# uproszczony_odbiornik.net
KiCad netlist of a schematic drawn in EAGLE
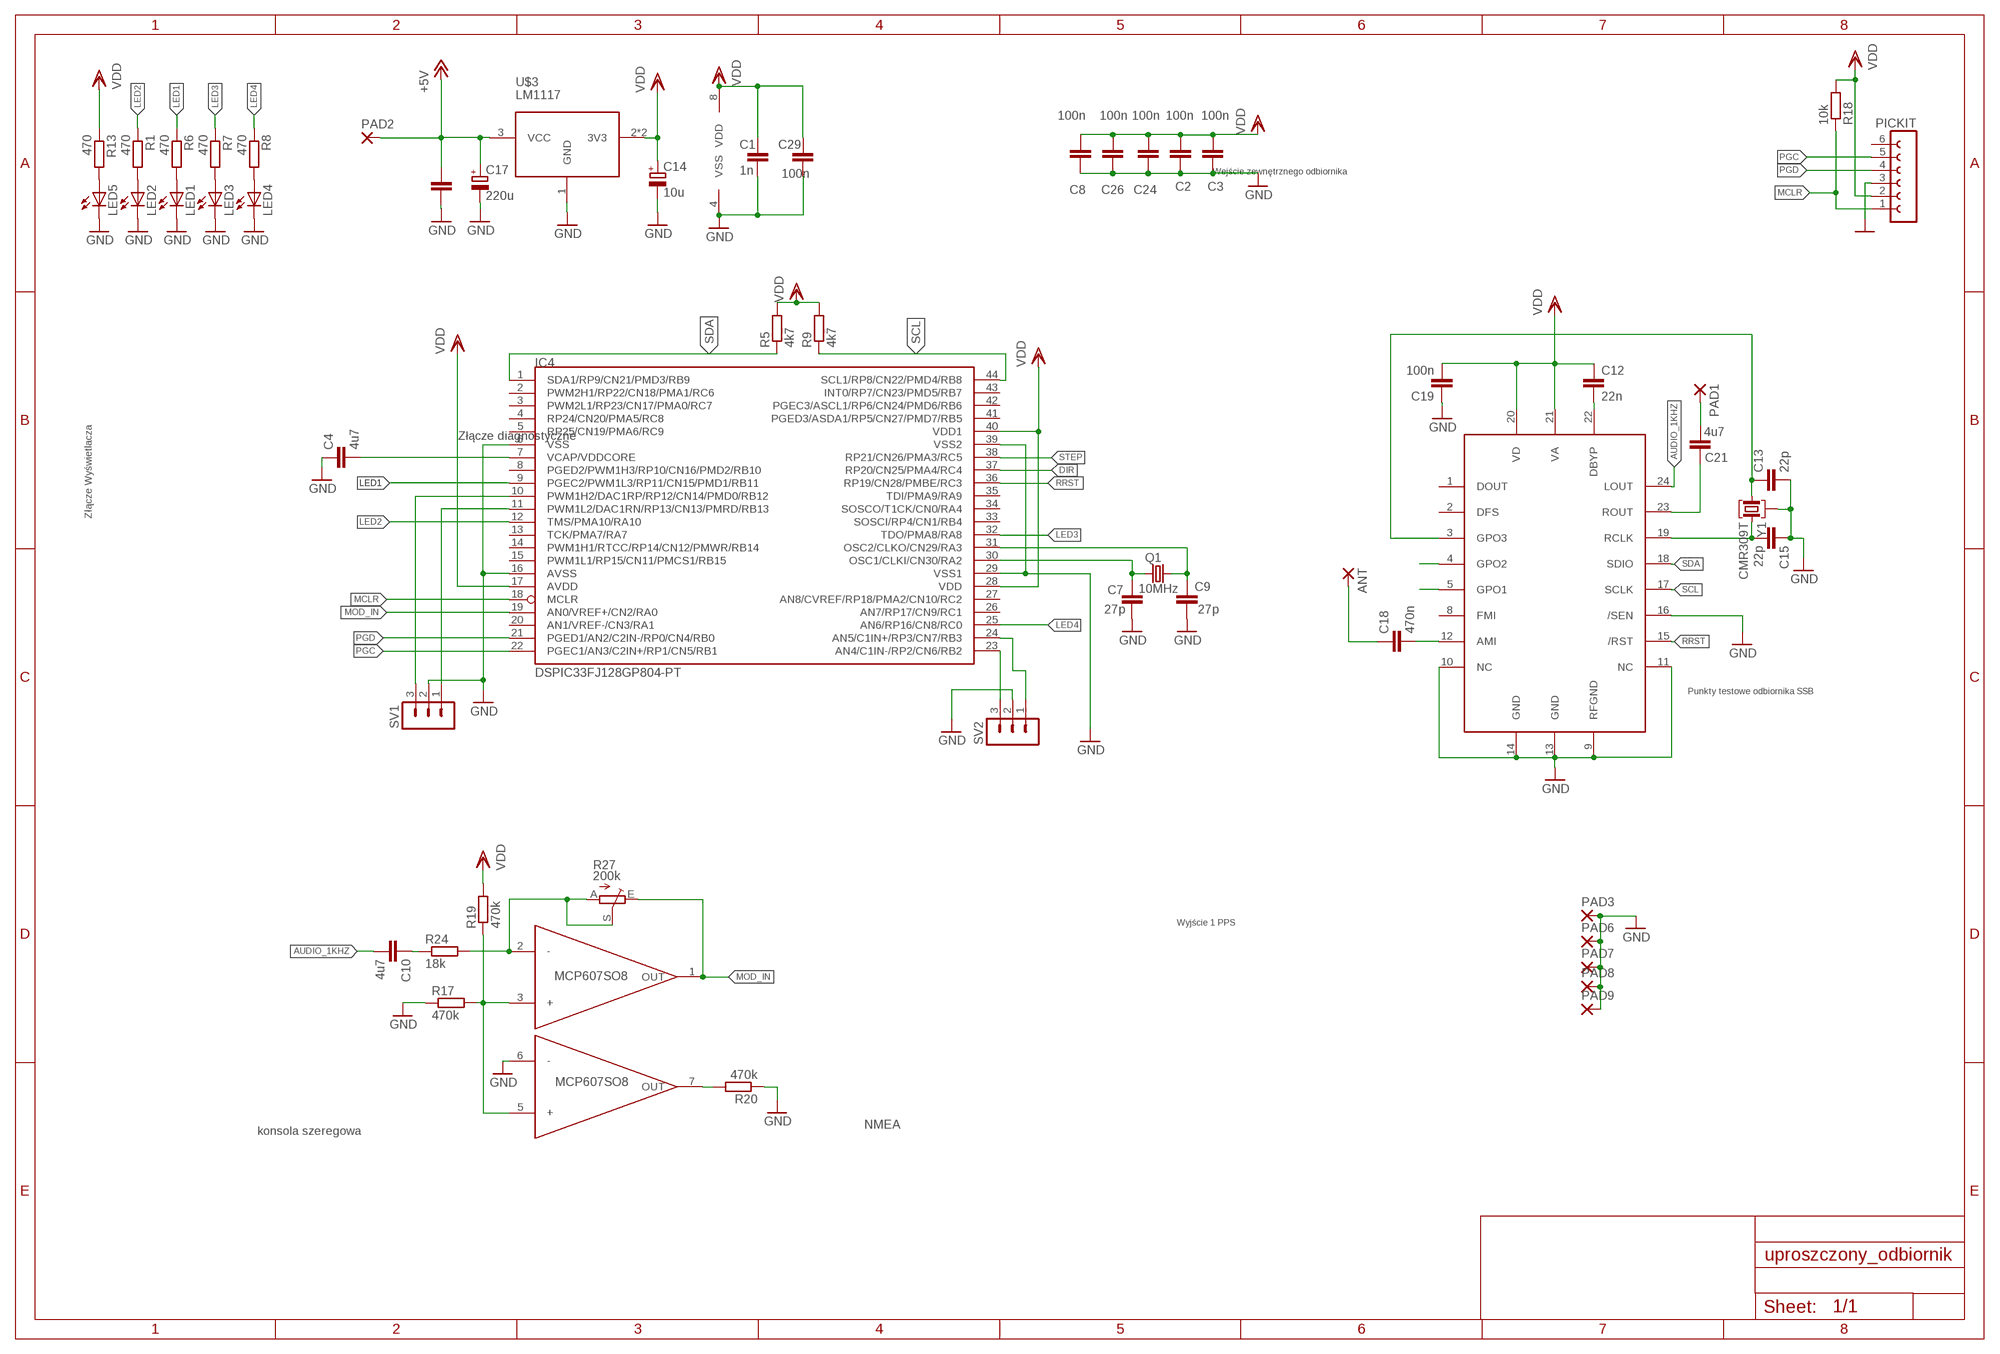
[diagram p0: schematic, sheet 1]

(export (version "E")
  (design (tool "Eeschema 10.0.6"))
  (components
    (comp (ref "ANT")
      (value "1,6/0,9")
      (footprint "eagle-import:1,6_0,9")
      (libsource (lib "eagle-import") (part "1,6/0,9"))
    )
    (comp (ref "C1")
      (value "1n")
      (footprint "eagle-import:C0805K")
      (libsource (lib "eagle-import") (part "C-EUC0805K"))
    )
    (comp (ref "C2")
      (value "100n")
      (footprint "eagle-import:C0805K")
      (libsource (lib "eagle-import") (part "C-EUC0805K"))
    )
    (comp (ref "C3")
      (value "100n")
      (footprint "eagle-import:C0805K")
      (libsource (lib "eagle-import") (part "C-EUC0805K"))
    )
    (comp (ref "C4")
      (value "4u7")
      (footprint "eagle-import:C0805K")
      (libsource (lib "eagle-import") (part "C-EUC0805K"))
    )
    (comp (ref "C5")
      (value "100n")
      (footprint "eagle-import:C0805K")
      (libsource (lib "eagle-import") (part "C-EUC0805K"))
    )
    (comp (ref "C7")
      (value "27p")
      (footprint "eagle-import:C0805K")
      (libsource (lib "eagle-import") (part "C-EUC0805K"))
    )
    (comp (ref "C8")
      (value "100n")
      (footprint "eagle-import:C0805K")
      (libsource (lib "eagle-import") (part "C-EUC0805K"))
    )
    (comp (ref "C9")
      (value "27p")
      (footprint "eagle-import:C0805K")
      (libsource (lib "eagle-import") (part "C-EUC0805K"))
    )
    (comp (ref "C10")
      (value "4u7")
      (footprint "eagle-import:C0603K")
      (libsource (lib "eagle-import") (part "C-EUC0603K"))
    )
    (comp (ref "C12")
      (value "22n")
      (footprint "eagle-import:C0603K")
      (libsource (lib "eagle-import") (part "C-EUC0603K"))
    )
    (comp (ref "C13")
      (value "22p")
      (footprint "eagle-import:C0603K")
      (libsource (lib "eagle-import") (part "C-EUC0603K"))
    )
    (comp (ref "C14")
      (value "10u")
      (footprint "eagle-import:SMC_B")
      (libsource (lib "eagle-import") (part "CPOL-EUSMCB"))
    )
    (comp (ref "C15")
      (value "22p")
      (footprint "eagle-import:C0603K")
      (libsource (lib "eagle-import") (part "C-EUC0603K"))
    )
    (comp (ref "C17")
      (value "220u")
      (footprint "eagle-import:SMC_B")
      (libsource (lib "eagle-import") (part "CPOL-EUSMCB"))
    )
    (comp (ref "C18")
      (value "470n")
      (footprint "eagle-import:C0603K")
      (libsource (lib "eagle-import") (part "C-EUC0603K"))
    )
    (comp (ref "C19")
      (value "100n")
      (footprint "eagle-import:C0603K")
      (libsource (lib "eagle-import") (part "C-EUC0603K"))
    )
    (comp (ref "C21")
      (value "4u7")
      (footprint "eagle-import:C0603K")
      (libsource (lib "eagle-import") (part "C-EUC0603K"))
    )
    (comp (ref "C24")
      (value "100n")
      (footprint "eagle-import:C0805K")
      (libsource (lib "eagle-import") (part "C-EUC0805K"))
    )
    (comp (ref "C26")
      (value "100n")
      (footprint "eagle-import:C0805K")
      (libsource (lib "eagle-import") (part "C-EUC0805K"))
    )
    (comp (ref "C29")
      (value "100n")
      (footprint "eagle-import:C0805K")
      (libsource (lib "eagle-import") (part "C-EUC0805K"))
    )
    (comp (ref "IC4")
      (value "DSPIC33FJ128GP804-PT")
      (footprint "eagle-import:TQFP44")
      (libsource (lib "eagle-import") (part "DSPIC33FJ64MC804-PT"))
    )
    (comp (ref "LED1")
      (value "LEDCHIP-LED0805")
      (footprint "eagle-import:CHIP-LED0805")
      (libsource (lib "eagle-import") (part "LEDCHIP-LED0805"))
    )
    (comp (ref "LED2")
      (value "LEDCHIP-LED0805")
      (footprint "eagle-import:CHIP-LED0805")
      (libsource (lib "eagle-import") (part "LEDCHIP-LED0805"))
    )
    (comp (ref "LED3")
      (value "LEDCHIP-LED0805")
      (footprint "eagle-import:CHIP-LED0805")
      (libsource (lib "eagle-import") (part "LEDCHIP-LED0805"))
    )
    (comp (ref "LED4")
      (value "LEDCHIP-LED0805")
      (footprint "eagle-import:CHIP-LED0805")
      (libsource (lib "eagle-import") (part "LEDCHIP-LED0805"))
    )
    (comp (ref "LED5")
      (value "LEDCHIP-LED0805")
      (footprint "eagle-import:CHIP-LED0805")
      (libsource (lib "eagle-import") (part "LEDCHIP-LED0805"))
    )
    (comp (ref "PAD1")
      (value "1,6/0,9")
      (footprint "eagle-import:1,6_0,9")
      (libsource (lib "eagle-import") (part "1,6/0,9"))
    )
    (comp (ref "PAD2")
      (value "1,6/0,9")
      (footprint "eagle-import:1,6_0,9")
      (libsource (lib "eagle-import") (part "1,6/0,9"))
    )
    (comp (ref "PAD3")
      (value "1,6/0,9")
      (footprint "eagle-import:1,6_0,9")
      (libsource (lib "eagle-import") (part "1,6/0,9"))
    )
    (comp (ref "PAD6")
      (value "1,6/0,9")
      (footprint "eagle-import:1,6_0,9")
      (libsource (lib "eagle-import") (part "1,6/0,9"))
    )
    (comp (ref "PAD7")
      (value "1,6/0,9")
      (footprint "eagle-import:1,6_0,9")
      (libsource (lib "eagle-import") (part "1,6/0,9"))
    )
    (comp (ref "PAD8")
      (value "1,6/0,9")
      (footprint "eagle-import:1,6_0,9")
      (libsource (lib "eagle-import") (part "1,6/0,9"))
    )
    (comp (ref "PAD9")
      (value "1,6/0,9")
      (footprint "eagle-import:1,6_0,9")
      (libsource (lib "eagle-import") (part "1,6/0,9"))
    )
    (comp (ref "PICKIT")
      (value "FE06-1")
      (footprint "eagle-import:FE06")
      (libsource (lib "eagle-import") (part "FE06-1"))
    )
    (comp (ref "Q1")
      (value "10MHz")
      (footprint "eagle-import:HC49U-V")
      (libsource (lib "eagle-import") (part "CRYSTALHC49U-V"))
    )
    (comp (ref "R1")
      (value "470")
      (footprint "eagle-import:R0805")
      (libsource (lib "eagle-import") (part "R-EU_R0805"))
    )
    (comp (ref "R5")
      (value "4k7")
      (footprint "eagle-import:R0805")
      (libsource (lib "eagle-import") (part "R-EU_R0805"))
    )
    (comp (ref "R6")
      (value "470")
      (footprint "eagle-import:R0805")
      (libsource (lib "eagle-import") (part "R-EU_R0805"))
    )
    (comp (ref "R7")
      (value "470")
      (footprint "eagle-import:R0805")
      (libsource (lib "eagle-import") (part "R-EU_R0805"))
    )
    (comp (ref "R8")
      (value "470")
      (footprint "eagle-import:R0805")
      (libsource (lib "eagle-import") (part "R-EU_R0805"))
    )
    (comp (ref "R9")
      (value "4k7")
      (footprint "eagle-import:R0805")
      (libsource (lib "eagle-import") (part "R-EU_R0805"))
    )
    (comp (ref "R13")
      (value "470")
      (footprint "eagle-import:R0805")
      (libsource (lib "eagle-import") (part "R-EU_R0805"))
    )
    (comp (ref "R17")
      (value "470k")
      (footprint "eagle-import:M0805")
      (libsource (lib "eagle-import") (part "R-EU_M0805"))
    )
    (comp (ref "R18")
      (value "10k")
      (footprint "eagle-import:R0805")
      (libsource (lib "eagle-import") (part "R-EU_R0805"))
    )
    (comp (ref "R19")
      (value "470k")
      (footprint "eagle-import:M0805")
      (libsource (lib "eagle-import") (part "R-EU_M0805"))
    )
    (comp (ref "R20")
      (value "470k")
      (footprint "eagle-import:M0805")
      (libsource (lib "eagle-import") (part "R-EU_M0805"))
    )
    (comp (ref "R24")
      (value "18k")
      (footprint "eagle-import:M0805")
      (libsource (lib "eagle-import") (part "R-EU_M0805"))
    )
    (comp (ref "R27")
      (value "200k")
      (footprint "eagle-import:RJ9W")
      (libsource (lib "eagle-import") (part "TRIM_EU-RJ9W"))
    )
    (comp (ref "SV1")
      (value "MA03-1")
      (footprint "eagle-import:MA03-1")
      (libsource (lib "eagle-import") (part "MA03-1"))
    )
    (comp (ref "SV2")
      (value "MA03-1")
      (footprint "eagle-import:MA03-1")
      (libsource (lib "eagle-import") (part "MA03-1"))
    )
    (comp (ref "U$1")
      (value "MCP607SO8")
      (footprint "eagle-import:SOIC8")
      (libsource (lib "eagle-import") (part "MCP607SO8"))
    )
    (comp (ref "U$3")
      (value "LM1117")
      (footprint "eagle-import:SOT223-3")
      (libsource (lib "eagle-import") (part "LM1117"))
    )
    (comp (ref "U$5")
      (value "SI4735-D60")
      (footprint "eagle-import:SSOP24")
      (libsource (lib "eagle-import") (part "SI4735-D60"))
    )
    (comp (ref "Y1")
      (value "CMR309T")
      (footprint "eagle-import:CMR309T")
      (libsource (lib "eagle-import") (part "CMR309T"))
    )
  )
  (nets
    (net (code "1") (name "+5V") (class "Default")
      (node (ref "C17") (pin "+") (pinfunction "+_+") (pintype "passive"))
      (node (ref "C5") (pin "1") (pinfunction "1_1") (pintype "passive"))
      (node (ref "PAD2") (pin "1") (pinfunction "P_1") (pintype "passive"))
      (node (ref "U$3") (pin "3") (pinfunction "VCC_3") (pintype "power_in"))
    )
    (net (code "2") (name "AUDIO_1KHZ") (class "Default")
      (node (ref "C10") (pin "2") (pinfunction "2_2") (pintype "passive"))
      (node (ref "U$5") (pin "24") (pinfunction "LOUT_24") (pintype "power_in"))
    )
    (net (code "3") (name "DIR") (class "Default")
      (node (ref "IC4") (pin "37") (pinfunction "RP20/CN25/PMA4/RC4_37") (pintype "bidirectional"))
    )
    (net (code "4") (name "GND") (class "Default")
      (node (ref "C1") (pin "2") (pinfunction "2_2") (pintype "passive"))
      (node (ref "C13") (pin "2") (pinfunction "2_2") (pintype "passive"))
      (node (ref "C14") (pin "-") (pinfunction "-_-") (pintype "passive"))
      (node (ref "C15") (pin "1") (pinfunction "1_1") (pintype "passive"))
      (node (ref "C17") (pin "-") (pinfunction "-_-") (pintype "passive"))
      (node (ref "C19") (pin "1") (pinfunction "1_1") (pintype "passive"))
      (node (ref "C2") (pin "2") (pinfunction "2_2") (pintype "passive"))
      (node (ref "C24") (pin "1") (pinfunction "1_1") (pintype "passive"))
      (node (ref "C26") (pin "1") (pinfunction "1_1") (pintype "passive"))
      (node (ref "C29") (pin "2") (pinfunction "2_2") (pintype "passive"))
      (node (ref "C3") (pin "2") (pinfunction "2_2") (pintype "passive"))
      (node (ref "C4") (pin "1") (pinfunction "1_1") (pintype "passive"))
      (node (ref "C5") (pin "2") (pinfunction "2_2") (pintype "passive"))
      (node (ref "C7") (pin "2") (pinfunction "2_2") (pintype "passive"))
      (node (ref "C8") (pin "1") (pinfunction "1_1") (pintype "passive"))
      (node (ref "C9") (pin "2") (pinfunction "2_2") (pintype "passive"))
      (node (ref "IC4") (pin "16") (pinfunction "AVSS_16") (pintype "power_in"))
      (node (ref "IC4") (pin "29") (pinfunction "VSS1_29") (pintype "power_in"))
      (node (ref "IC4") (pin "39") (pinfunction "VSS2_39") (pintype "power_in"))
      (node (ref "IC4") (pin "6") (pinfunction "VSS_6") (pintype "power_in"))
      (node (ref "LED1") (pin "C") (pinfunction "C_C") (pintype "passive"))
      (node (ref "LED2") (pin "C") (pinfunction "C_C") (pintype "passive"))
      (node (ref "LED3") (pin "C") (pinfunction "C_C") (pintype "passive"))
      (node (ref "LED4") (pin "C") (pinfunction "C_C") (pintype "passive"))
      (node (ref "LED5") (pin "C") (pinfunction "C_C") (pintype "passive"))
      (node (ref "PAD3") (pin "1") (pinfunction "P_1") (pintype "passive"))
      (node (ref "PAD6") (pin "1") (pinfunction "P_1") (pintype "passive"))
      (node (ref "PAD7") (pin "1") (pinfunction "P_1") (pintype "passive"))
      (node (ref "PAD8") (pin "1") (pinfunction "P_1") (pintype "passive"))
      (node (ref "PAD9") (pin "1") (pinfunction "P_1") (pintype "passive"))
      (node (ref "PICKIT") (pin "3") (pinfunction "3_3") (pintype "passive"))
      (node (ref "R17") (pin "1") (pinfunction "1_1") (pintype "passive"))
      (node (ref "R20") (pin "1") (pinfunction "1_1") (pintype "passive"))
      (node (ref "SV1") (pin "2") (pinfunction "2_2") (pintype "passive"))
      (node (ref "SV2") (pin "2") (pinfunction "2_2") (pintype "passive"))
      (node (ref "U$1") (pin "4") (pinfunction "VSS_4") (pintype "power_in"))
      (node (ref "U$1") (pin "6") (pinfunction "-_6") (pintype "input"))
      (node (ref "U$3") (pin "1") (pinfunction "GND_1") (pintype "power_in"))
      (node (ref "U$5") (pin "10") (pinfunction "NC_10") (pintype "power_in"))
      (node (ref "U$5") (pin "11") (pinfunction "NC_11") (pintype "power_in"))
      (node (ref "U$5") (pin "13") (pinfunction "GND_13") (pintype "power_in"))
      (node (ref "U$5") (pin "14") (pinfunction "GND_14") (pintype "power_in"))
      (node (ref "U$5") (pin "16") (pinfunction "/SEN_16") (pintype "input"))
      (node (ref "U$5") (pin "9") (pinfunction "RFGND_9") (pintype "power_in"))
      (node (ref "Y1") (pin "3") (pinfunction "G_3") (pintype "passive"))
    )
    (net (code "5") (name "LED1") (class "Default")
      (node (ref "IC4") (pin "9") (pinfunction "PGEC2/PWM1L3/RP11/CN15/PMD1/RB11_9") (pintype "bidirectional"))
      (node (ref "R6") (pin "1") (pinfunction "1_1") (pintype "passive"))
    )
    (net (code "6") (name "LED2") (class "Default")
      (node (ref "IC4") (pin "12") (pinfunction "TMS/PMA10/RA10_12") (pintype "bidirectional"))
      (node (ref "R1") (pin "1") (pinfunction "1_1") (pintype "passive"))
    )
    (net (code "7") (name "LED3") (class "Default")
      (node (ref "IC4") (pin "32") (pinfunction "TDO/PMA8/RA8_32") (pintype "bidirectional"))
      (node (ref "R7") (pin "1") (pinfunction "1_1") (pintype "passive"))
    )
    (net (code "8") (name "LED4") (class "Default")
      (node (ref "IC4") (pin "25") (pinfunction "AN6/RP16/CN8/RC0_25") (pintype "bidirectional"))
      (node (ref "R8") (pin "1") (pinfunction "1_1") (pintype "passive"))
    )
    (net (code "9") (name "MCLR") (class "Default")
      (node (ref "IC4") (pin "18") (pinfunction "MCLR_18") (pintype "input"))
      (node (ref "PICKIT") (pin "1") (pinfunction "1_1") (pintype "passive"))
      (node (ref "R18") (pin "1") (pinfunction "1_1") (pintype "passive"))
    )
    (net (code "10") (name "MOD_IN") (class "Default")
      (node (ref "IC4") (pin "19") (pinfunction "AN0/VREF+/CN2/RA0_19") (pintype "bidirectional"))
      (node (ref "R27") (pin "E") (pinfunction "E_E") (pintype "passive"))
      (node (ref "U$1") (pin "1") (pinfunction "OUT_1") (pintype "output"))
    )
    (net (code "11") (name "Net-(ANT-P)") (class "Default")
      (node (ref "ANT") (pin "1") (pinfunction "P_1") (pintype "passive"))
      (node (ref "C18") (pin "1") (pinfunction "1_1") (pintype "passive"))
    )
    (net (code "12") (name "Net-(C10-Pad1)") (class "Default")
      (node (ref "C10") (pin "1") (pinfunction "1_1") (pintype "passive"))
      (node (ref "R24") (pin "1") (pinfunction "1_1") (pintype "passive"))
    )
    (net (code "13") (name "Net-(IC4-AN4{slash}C1IN-{slash}RP2{slash}CN6{slash}RB2)") (class "Default")
      (node (ref "IC4") (pin "23") (pinfunction "AN4/C1IN-/RP2/CN6/RB2_23") (pintype "bidirectional"))
      (node (ref "SV2") (pin "3") (pinfunction "3_3") (pintype "passive"))
    )
    (net (code "14") (name "Net-(IC4-AN5{slash}C1IN+{slash}RP3{slash}CN7{slash}RB3)") (class "Default")
      (node (ref "IC4") (pin "24") (pinfunction "AN5/C1IN+/RP3/CN7/RB3_24") (pintype "bidirectional"))
      (node (ref "SV2") (pin "1") (pinfunction "1_1") (pintype "passive"))
    )
    (net (code "15") (name "Net-(IC4-OSC1{slash}CLKI{slash}CN30{slash}RA2)") (class "Default")
      (node (ref "C7") (pin "1") (pinfunction "1_1") (pintype "passive"))
      (node (ref "IC4") (pin "30") (pinfunction "OSC1/CLKI/CN30/RA2_30") (pintype "bidirectional"))
      (node (ref "Q1") (pin "1") (pinfunction "1_1") (pintype "passive"))
    )
    (net (code "16") (name "Net-(IC4-OSC2{slash}CLKO{slash}CN29{slash}RA3)") (class "Default")
      (node (ref "C9") (pin "1") (pinfunction "1_1") (pintype "passive"))
      (node (ref "IC4") (pin "31") (pinfunction "OSC2/CLKO/CN29/RA3_31") (pintype "bidirectional"))
      (node (ref "Q1") (pin "2") (pinfunction "2_2") (pintype "passive"))
    )
    (net (code "17") (name "Net-(IC4-PWM1H2{slash}DAC1RP{slash}RP12{slash}CN14{slash}PMD0{slash}RB12)") (class "Default")
      (node (ref "IC4") (pin "10") (pinfunction "PWM1H2/DAC1RP/RP12/CN14/PMD0/RB12_10") (pintype "bidirectional"))
      (node (ref "SV1") (pin "3") (pinfunction "3_3") (pintype "passive"))
    )
    (net (code "18") (name "Net-(IC4-PWM1L2{slash}DAC1RN{slash}RP13{slash}CN13{slash}PMRD{slash}RB13)") (class "Default")
      (node (ref "IC4") (pin "11") (pinfunction "PWM1L2/DAC1RN/RP13/CN13/PMRD/RB13_11") (pintype "bidirectional"))
      (node (ref "SV1") (pin "1") (pinfunction "1_1") (pintype "passive"))
    )
    (net (code "19") (name "Net-(IC4-VCAP{slash}VDDCORE)") (class "Default")
      (node (ref "C4") (pin "2") (pinfunction "2_2") (pintype "passive"))
      (node (ref "IC4") (pin "7") (pinfunction "VCAP/VDDCORE_7") (pintype "power_in"))
    )
    (net (code "20") (name "Net-(LED1-PadA)") (class "Default")
      (node (ref "LED1") (pin "A") (pinfunction "A_A") (pintype "passive"))
      (node (ref "R6") (pin "2") (pinfunction "2_2") (pintype "passive"))
    )
    (net (code "21") (name "Net-(LED2-PadA)") (class "Default")
      (node (ref "LED2") (pin "A") (pinfunction "A_A") (pintype "passive"))
      (node (ref "R1") (pin "2") (pinfunction "2_2") (pintype "passive"))
    )
    (net (code "22") (name "Net-(LED3-PadA)") (class "Default")
      (node (ref "LED3") (pin "A") (pinfunction "A_A") (pintype "passive"))
      (node (ref "R7") (pin "2") (pinfunction "2_2") (pintype "passive"))
    )
    (net (code "23") (name "Net-(LED4-PadA)") (class "Default")
      (node (ref "LED4") (pin "A") (pinfunction "A_A") (pintype "passive"))
      (node (ref "R8") (pin "2") (pinfunction "2_2") (pintype "passive"))
    )
    (net (code "24") (name "Net-(LED5-PadA)") (class "Default")
      (node (ref "LED5") (pin "A") (pinfunction "A_A") (pintype "passive"))
      (node (ref "R13") (pin "2") (pinfunction "2_2") (pintype "passive"))
    )
    (net (code "25") (name "Net-(PAD1-P)") (class "Default")
      (node (ref "C21") (pin "2") (pinfunction "2_2") (pintype "passive"))
      (node (ref "PAD1") (pin "1") (pinfunction "P_1") (pintype "passive"))
    )
    (net (code "26") (name "Net-(U$1A-+)") (class "Default")
      (node (ref "R17") (pin "2") (pinfunction "2_2") (pintype "passive"))
      (node (ref "R19") (pin "1") (pinfunction "1_1") (pintype "passive"))
      (node (ref "U$1") (pin "3") (pinfunction "+_3") (pintype "input"))
      (node (ref "U$1") (pin "5") (pinfunction "+_5") (pintype "input"))
    )
    (net (code "27") (name "Net-(U$1A--)") (class "Default")
      (node (ref "R24") (pin "2") (pinfunction "2_2") (pintype "passive"))
      (node (ref "R27") (pin "A") (pinfunction "A_A") (pintype "passive"))
      (node (ref "R27") (pin "S") (pinfunction "S_S") (pintype "passive"))
      (node (ref "U$1") (pin "2") (pinfunction "-_2") (pintype "input"))
    )
    (net (code "28") (name "Net-(U$1B-OUT)") (class "Default")
      (node (ref "R20") (pin "2") (pinfunction "2_2") (pintype "passive"))
      (node (ref "U$1") (pin "7") (pinfunction "OUT_7") (pintype "output"))
    )
    (net (code "29") (name "Net-(U$5-AMI)") (class "Default")
      (node (ref "C18") (pin "2") (pinfunction "2_2") (pintype "passive"))
      (node (ref "U$5") (pin "12") (pinfunction "AMI_12") (pintype "input"))
    )
    (net (code "30") (name "Net-(U$5-DBYP)") (class "Default")
      (node (ref "C12") (pin "2") (pinfunction "2_2") (pintype "passive"))
      (node (ref "U$5") (pin "22") (pinfunction "DBYP_22") (pintype "power_in"))
    )
    (net (code "31") (name "Net-(U$5-GPO3)") (class "Default")
      (node (ref "C13") (pin "1") (pinfunction "1_1") (pintype "passive"))
      (node (ref "U$5") (pin "3") (pinfunction "GPO3_3") (pintype "power_in"))
      (node (ref "Y1") (pin "1") (pinfunction "1_1") (pintype "passive"))
    )
    (net (code "32") (name "Net-(U$5-RCLK)") (class "Default")
      (node (ref "C15") (pin "2") (pinfunction "2_2") (pintype "passive"))
      (node (ref "U$5") (pin "19") (pinfunction "RCLK_19") (pintype "power_in"))
      (node (ref "Y1") (pin "2") (pinfunction "2_2") (pintype "passive"))
    )
    (net (code "33") (name "Net-(U$5-ROUT)") (class "Default")
      (node (ref "C21") (pin "1") (pinfunction "1_1") (pintype "passive"))
      (node (ref "U$5") (pin "23") (pinfunction "ROUT_23") (pintype "power_in"))
    )
    (net (code "34") (name "PGC") (class "Default")
      (node (ref "IC4") (pin "22") (pinfunction "PGEC1/AN3/C2IN+/RP1/CN5/RB1_22") (pintype "bidirectional"))
      (node (ref "PICKIT") (pin "5") (pinfunction "5_5") (pintype "passive"))
    )
    (net (code "35") (name "PGD") (class "Default")
      (node (ref "IC4") (pin "21") (pinfunction "PGED1/AN2/C2IN-/RP0/CN4/RB0_21") (pintype "bidirectional"))
      (node (ref "PICKIT") (pin "4") (pinfunction "4_4") (pintype "passive"))
    )
    (net (code "36") (name "RRST") (class "Default")
      (node (ref "IC4") (pin "36") (pinfunction "RP19/CN28/PMBE/RC3_36") (pintype "bidirectional"))
      (node (ref "U$5") (pin "15") (pinfunction "/RST_15") (pintype "input"))
    )
    (net (code "37") (name "SCL") (class "Default")
      (node (ref "IC4") (pin "44") (pinfunction "SCL1/RP8/CN22/PMD4/RB8_44") (pintype "bidirectional"))
      (node (ref "R9") (pin "1") (pinfunction "1_1") (pintype "passive"))
      (node (ref "U$5") (pin "17") (pinfunction "SCLK_17") (pintype "input"))
    )
    (net (code "38") (name "SDA") (class "Default")
      (node (ref "IC4") (pin "1") (pinfunction "SDA1/RP9/CN21/PMD3/RB9_1") (pintype "bidirectional"))
      (node (ref "R5") (pin "1") (pinfunction "1_1") (pintype "passive"))
      (node (ref "U$5") (pin "18") (pinfunction "SDIO_18") (pintype "bidirectional"))
    )
    (net (code "39") (name "STEP") (class "Default")
      (node (ref "IC4") (pin "38") (pinfunction "RP21/CN26/PMA3/RC5_38") (pintype "bidirectional"))
    )
    (net (code "40") (name "VDD") (class "Default")
      (node (ref "C1") (pin "1") (pinfunction "1_1") (pintype "passive"))
      (node (ref "C12") (pin "1") (pinfunction "1_1") (pintype "passive"))
      (node (ref "C14") (pin "+") (pinfunction "+_+") (pintype "passive"))
      (node (ref "C19") (pin "2") (pinfunction "2_2") (pintype "passive"))
      (node (ref "C2") (pin "1") (pinfunction "1_1") (pintype "passive"))
      (node (ref "C24") (pin "2") (pinfunction "2_2") (pintype "passive"))
      (node (ref "C26") (pin "2") (pinfunction "2_2") (pintype "passive"))
      (node (ref "C29") (pin "1") (pinfunction "1_1") (pintype "passive"))
      (node (ref "C3") (pin "1") (pinfunction "1_1") (pintype "passive"))
      (node (ref "C8") (pin "2") (pinfunction "2_2") (pintype "passive"))
      (node (ref "IC4") (pin "17") (pinfunction "AVDD_17") (pintype "power_in"))
      (node (ref "IC4") (pin "28") (pinfunction "VDD_28") (pintype "power_in"))
      (node (ref "IC4") (pin "40") (pinfunction "VDD1_40") (pintype "power_in"))
      (node (ref "PICKIT") (pin "2") (pinfunction "2_2") (pintype "passive"))
      (node (ref "R13") (pin "1") (pinfunction "1_1") (pintype "passive"))
      (node (ref "R18") (pin "2") (pinfunction "2_2") (pintype "passive"))
      (node (ref "R19") (pin "2") (pinfunction "2_2") (pintype "passive"))
      (node (ref "R5") (pin "2") (pinfunction "2_2") (pintype "passive"))
      (node (ref "R9") (pin "2") (pinfunction "2_2") (pintype "passive"))
      (node (ref "U$1") (pin "8") (pinfunction "VDD_8") (pintype "power_in"))
      (node (ref "U$3") (pin "2") (pinfunction "3V3_2") (pintype "output"))
      (node (ref "U$3") (pin "4") (pinfunction "3V3_4") (pintype "output"))
      (node (ref "U$5") (pin "20") (pinfunction "VD_20") (pintype "power_in"))
      (node (ref "U$5") (pin "21") (pinfunction "VA_21") (pintype "power_in"))
    )
    (net (code "41") (name "unconnected-(IC4-AN1{slash}VREF-{slash}CN3{slash}RA1-Pad20)") (class "Default")
      (node (ref "IC4") (pin "20") (pinfunction "AN1/VREF-/CN3/RA1_20") (pintype "bidirectional"))
    )
    (net (code "42") (name "unconnected-(IC4-AN7{slash}RP17{slash}CN9{slash}RC1-Pad26)") (class "Default")
      (node (ref "IC4") (pin "26") (pinfunction "AN7/RP17/CN9/RC1_26") (pintype "bidirectional"))
    )
    (net (code "43") (name "unconnected-(IC4-AN8{slash}CVREF{slash}RP18{slash}PMA2{slash}CN10{slash}RC2-Pad27)") (class "Default")
      (node (ref "IC4") (pin "27") (pinfunction "AN8/CVREF/RP18/PMA2/CN10/RC2_27") (pintype "bidirectional"))
    )
    (net (code "44") (name "unconnected-(IC4-INT0{slash}RP7{slash}CN23{slash}PMD5{slash}RB7-Pad43)") (class "Default")
      (node (ref "IC4") (pin "43") (pinfunction "INT0/RP7/CN23/PMD5/RB7_43") (pintype "bidirectional"))
    )
    (net (code "45") (name "unconnected-(IC4-PGEC3{slash}ASCL1{slash}RP6{slash}CN24{slash}PMD6{slash}RB6-Pad42)") (class "Default")
      (node (ref "IC4") (pin "42") (pinfunction "PGEC3/ASCL1/RP6/CN24/PMD6/RB6_42") (pintype "bidirectional"))
    )
    (net (code "46") (name "unconnected-(IC4-PGED2{slash}PWM1H3{slash}RP10{slash}CN16{slash}PMD2{slash}RB10-Pad8)") (class "Default")
      (node (ref "IC4") (pin "8") (pinfunction "PGED2/PWM1H3/RP10/CN16/PMD2/RB10_8") (pintype "bidirectional"))
    )
    (net (code "47") (name "unconnected-(IC4-PGED3{slash}ASDA1{slash}RP5{slash}CN27{slash}PMD7{slash}RB5-Pad41)") (class "Default")
      (node (ref "IC4") (pin "41") (pinfunction "PGED3/ASDA1/RP5/CN27/PMD7/RB5_41") (pintype "bidirectional"))
    )
    (net (code "48") (name "unconnected-(IC4-PWM1H1{slash}RTCC{slash}RP14{slash}CN12{slash}PMWR{slash}RB14-Pad14)") (class "Default")
      (node (ref "IC4") (pin "14") (pinfunction "PWM1H1/RTCC/RP14/CN12/PMWR/RB14_14") (pintype "bidirectional"))
    )
    (net (code "49") (name "unconnected-(IC4-PWM1L1{slash}RP15{slash}CN11{slash}PMCS1{slash}RB15-Pad15)") (class "Default")
      (node (ref "IC4") (pin "15") (pinfunction "PWM1L1/RP15/CN11/PMCS1/RB15_15") (pintype "bidirectional"))
    )
    (net (code "50") (name "unconnected-(IC4-PWM2H1{slash}RP22{slash}CN18{slash}PMA1{slash}RC6-Pad2)") (class "Default")
      (node (ref "IC4") (pin "2") (pinfunction "PWM2H1/RP22/CN18/PMA1/RC6_2") (pintype "bidirectional"))
    )
    (net (code "51") (name "unconnected-(IC4-PWM2L1{slash}RP23{slash}CN17{slash}PMA0{slash}RC7-Pad3)") (class "Default")
      (node (ref "IC4") (pin "3") (pinfunction "PWM2L1/RP23/CN17/PMA0/RC7_3") (pintype "bidirectional"))
    )
    (net (code "52") (name "unconnected-(IC4-RP24{slash}CN20{slash}PMA5{slash}RC8-Pad4)") (class "Default")
      (node (ref "IC4") (pin "4") (pinfunction "RP24/CN20/PMA5/RC8_4") (pintype "bidirectional"))
    )
    (net (code "53") (name "unconnected-(IC4-RP25{slash}CN19{slash}PMA6{slash}RC9-Pad5)") (class "Default")
      (node (ref "IC4") (pin "5") (pinfunction "RP25/CN19/PMA6/RC9_5") (pintype "bidirectional"))
    )
    (net (code "54") (name "unconnected-(IC4-SOSCI{slash}RP4{slash}CN1{slash}RB4-Pad33)") (class "Default")
      (node (ref "IC4") (pin "33") (pinfunction "SOSCI/RP4/CN1/RB4_33") (pintype "bidirectional"))
    )
    (net (code "55") (name "unconnected-(IC4-SOSCO{slash}T1CK{slash}CN0{slash}RA4-Pad34)") (class "Default")
      (node (ref "IC4") (pin "34") (pinfunction "SOSCO/T1CK/CN0/RA4_34") (pintype "bidirectional"))
    )
    (net (code "56") (name "unconnected-(IC4-TCK{slash}PMA7{slash}RA7-Pad13)") (class "Default")
      (node (ref "IC4") (pin "13") (pinfunction "TCK/PMA7/RA7_13") (pintype "bidirectional"))
    )
    (net (code "57") (name "unconnected-(IC4-TDI{slash}PMA9{slash}RA9-Pad35)") (class "Default")
      (node (ref "IC4") (pin "35") (pinfunction "TDI/PMA9/RA9_35") (pintype "bidirectional"))
    )
    (net (code "58") (name "unconnected-(PICKIT-Pad6)") (class "Default")
      (node (ref "PICKIT") (pin "6") (pinfunction "6_6") (pintype "passive"))
    )
    (net (code "59") (name "unconnected-(U$5-DFS-Pad2)") (class "Default")
      (node (ref "U$5") (pin "2") (pinfunction "DFS_2") (pintype "input"))
    )
    (net (code "60") (name "unconnected-(U$5-DOUT-Pad1)") (class "Default")
      (node (ref "U$5") (pin "1") (pinfunction "DOUT_1") (pintype "output"))
    )
    (net (code "61") (name "unconnected-(U$5-FMI-Pad8)") (class "Default")
      (node (ref "U$5") (pin "8") (pinfunction "FMI_8") (pintype "input"))
    )
    (net (code "62") (name "unconnected-(U$5-GPO1-Pad5)") (class "Default")
      (node (ref "U$5") (pin "5") (pinfunction "GPO1_5") (pintype "power_in"))
    )
    (net (code "63") (name "unconnected-(U$5-GPO2-Pad4)") (class "Default")
      (node (ref "U$5") (pin "4") (pinfunction "GPO2_4") (pintype "power_in"))
    )
  )
)
